# OutPut.net
KiCad netlist of a schematic drawn in Altium Designer
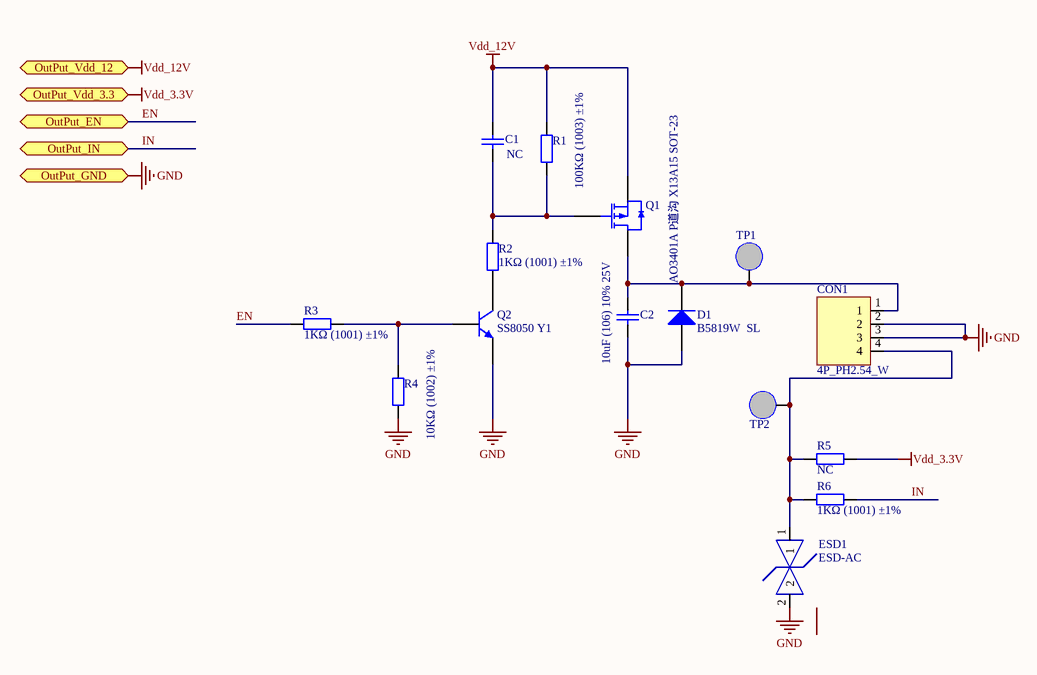
[diagram p0: OutPut.SchDoc]

(export (version "E")
  (design (tool "Eeschema 10.0.6"))
  (components
    (comp (ref "C1")
      (value "NC")
      (footprint "0805_C")
      (description "贴片电容")
      (libsource (lib "Miscellaneous Devices LC") (part "0805 22uF (226) 20% 25V"))
    )
    (comp (ref "C2")
      (value "10uF (106) 10% 25V")
      (footprint "0805_C")
      (description "贴片电容")
      (libsource (lib "Miscellaneous Devices LC") (part "0805 10uF (106) 10% 25V"))
    )
    (comp (ref "CON1")
      (value "4P_PH2.54_W")
      (footprint "PH2.0-WS-4P")
      (libsource (lib "mylib") (part "4P_XH2.54_W"))
    )
    (comp (ref "D1")
      (value "B5819W  SL")
      (footprint "SOD-123")
      (description "肖特基二极管")
      (libsource (lib "Miscellaneous Devices LC") (part "SOD-123 B5819W  SL"))
    )
    (comp (ref "ESD1") (value "ESD-AC") (footprint "SOD-523") (libsource (lib "mylib") (part "ESD-AC")))
    (comp (ref "Q1")
      (value "AO3401A P道沟 X13A15 SOT-23")
      (footprint "SOT-23-3L")
      (description "MOS(场效应管)")
      (libsource (lib "Miscellaneous Devices LC") (part "AO3401A P道沟 X13A15 SOT-23"))
    )
    (comp (ref "Q2")
      (value "SS8050 Y1")
      (footprint "SOT-23(SOT-23-3)")
      (description "三极管")
      (libsource (lib "Miscellaneous Devices LC") (part "SOT-23 SS8050 Y1"))
    )
    (comp (ref "R1")
      (value "100KΩ (1003) ±1%")
      (footprint "0805_R")
      (description "贴片电阻")
      (libsource (lib "Miscellaneous Devices LC") (part "0805 100KΩ (1003) 1%"))
    )
    (comp (ref "R2")
      (value "1KΩ (1001) ±1%")
      (footprint "0805_R")
      (description "贴片电阻")
      (libsource (lib "") (part "0805 1KΩ (1001) 1%_1"))
    )
    (comp (ref "R3")
      (value "1KΩ (1001) ±1%")
      (footprint "0805_R")
      (description "贴片电阻")
      (libsource (lib "Miscellaneous Devices LC") (part "0805 1KΩ (1001) 1%"))
    )
    (comp (ref "R4")
      (value "10KΩ (1002) ±1%")
      (footprint "0805_R")
      (description "贴片电阻")
      (libsource (lib "Miscellaneous Devices LC") (part "0805 10KΩ (1002) 1%"))
    )
    (comp (ref "R5")
      (value "NC")
      (footprint "0805_R")
      (description "贴片电阻")
      (libsource (lib "Miscellaneous Devices LC") (part "0805 1KΩ (1001) 1%"))
    )
    (comp (ref "R6")
      (value "1KΩ (1001) ±1%")
      (footprint "0805_R")
      (description "贴片电阻")
      (libsource (lib "Miscellaneous Devices LC") (part "0805 1KΩ (1001) 1%"))
    )
    (comp (ref "TP1") (value "TP") (footprint "TP") (libsource (lib "mylib") (part "TP")))
    (comp (ref "TP2") (value "TP") (footprint "TP") (libsource (lib "mylib") (part "TP")))
  )
  (nets
    (net (code "1") (name "/EN") (class "Default")
      (node (ref "R3") (pin "1") (pinfunction "1_1") (pintype "passive"))
    )
    (net (code "2") (name "/IN") (class "Default")
      (node (ref "R6") (pin "2") (pinfunction "2_2") (pintype "passive"))
    )
    (net (code "3") (name "GND") (class "Default")
      (node (ref "C2") (pin "1") (pinfunction "1_1") (pintype "passive"))
      (node (ref "CON1") (pin "2") (pinfunction "2_2") (pintype "passive"))
      (node (ref "CON1") (pin "3") (pinfunction "3_3") (pintype "passive"))
      (node (ref "D1") (pin "1") (pinfunction "A_1") (pintype "passive"))
      (node (ref "ESD1") (pin "2") (pinfunction "2_2") (pintype "passive"))
      (node (ref "Q2") (pin "2") (pinfunction "E_2") (pintype "passive"))
      (node (ref "R4") (pin "1") (pinfunction "1_1") (pintype "passive"))
    )
    (net (code "4") (name "Net-(CON1-Pad4)") (class "Default")
      (node (ref "CON1") (pin "4") (pinfunction "4_4") (pintype "passive"))
      (node (ref "ESD1") (pin "1") (pinfunction "1_1") (pintype "passive"))
      (node (ref "R5") (pin "1") (pinfunction "1_1") (pintype "passive"))
      (node (ref "R6") (pin "1") (pinfunction "1_1") (pintype "passive"))
      (node (ref "TP2") (pin "1") (pinfunction "1_1") (pintype "passive"))
    )
    (net (code "5") (name "Net-(D1-K)") (class "Default")
      (node (ref "C2") (pin "2") (pinfunction "2_2") (pintype "passive"))
      (node (ref "CON1") (pin "1") (pinfunction "1_1") (pintype "passive"))
      (node (ref "D1") (pin "2") (pinfunction "K_2") (pintype "passive"))
      (node (ref "Q1") (pin "3") (pinfunction "D_3") (pintype "passive"))
      (node (ref "TP1") (pin "1") (pinfunction "1_1") (pintype "passive"))
    )
    (net (code "6") (name "Net-(Q1-G)") (class "Default")
      (node (ref "C1") (pin "1") (pinfunction "1_1") (pintype "passive"))
      (node (ref "Q1") (pin "1") (pinfunction "G_1") (pintype "passive"))
      (node (ref "R1") (pin "1") (pinfunction "1_1") (pintype "passive"))
      (node (ref "R2") (pin "1") (pinfunction "1_1") (pintype "passive"))
    )
    (net (code "7") (name "Net-(Q2-B)") (class "Default")
      (node (ref "Q2") (pin "1") (pinfunction "B_1") (pintype "passive"))
      (node (ref "R3") (pin "2") (pinfunction "2_2") (pintype "passive"))
      (node (ref "R4") (pin "2") (pinfunction "2_2") (pintype "passive"))
    )
    (net (code "8") (name "Net-(Q2-C)") (class "Default")
      (node (ref "Q2") (pin "3") (pinfunction "C_3") (pintype "passive"))
      (node (ref "R2") (pin "2") (pinfunction "2_2") (pintype "passive"))
    )
    (net (code "9") (name "Vdd_3.3V") (class "Default")
      (node (ref "R5") (pin "2") (pinfunction "2_2") (pintype "passive"))
    )
    (net (code "10") (name "Vdd_12V") (class "Default")
      (node (ref "C1") (pin "2") (pinfunction "2_2") (pintype "passive"))
      (node (ref "Q1") (pin "2") (pinfunction "S_2") (pintype "passive"))
      (node (ref "R1") (pin "2") (pinfunction "2_2") (pintype "passive"))
    )
    (net (code "11") (name "unconnected-(CON1-PadA)") (class "Default")
      (node (ref "CON1") (pin "A") (pinfunction "A_A") (pintype "passive"))
    )
    (net (code "12") (name "unconnected-(CON1-PadB)") (class "Default")
      (node (ref "CON1") (pin "B") (pinfunction "B_B") (pintype "passive"))
    )
  )
)
